# Power_supply.net
KiCad netlist of a schematic drawn in Altium Designer
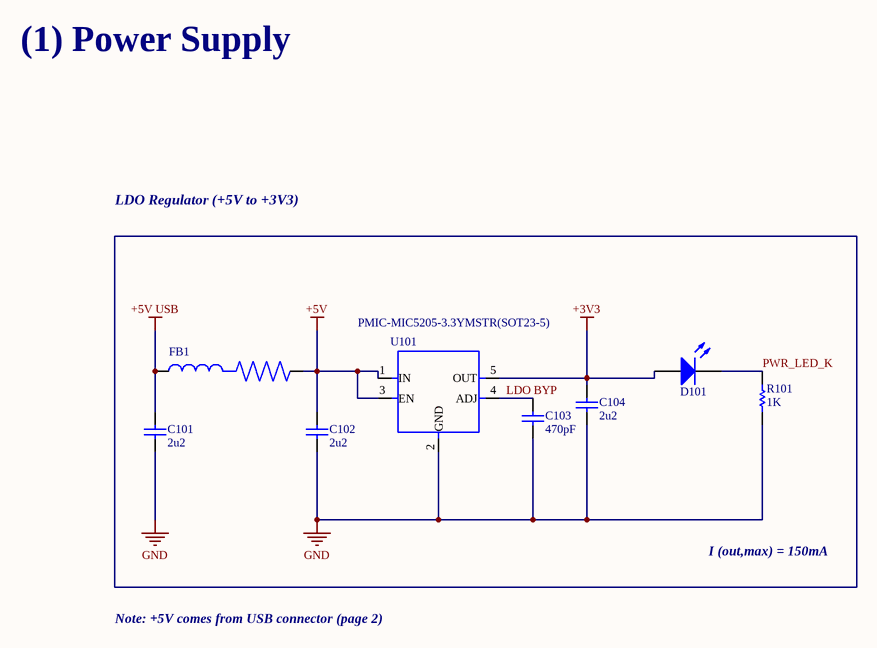
[diagram p0: Power_supply.SchDoc]

(export (version "E")
  (design (tool "Eeschema 10.0.6"))
  (components
    (comp (ref "C101")
      (value "2u2")
      (footprint "CAP-SM-0805")
      (description "Capacitor")
      (fields (field (name "Comment") "Cap Non-Pol SMD"))
      (libsource (lib "PIF_Library") (part "Cap Non-Pol SMD"))
    )
    (comp (ref "C102")
      (value "2u2")
      (footprint "CAP-SM-0805")
      (description "Capacitor")
      (fields (field (name "Comment") "Cap Non-Pol SMD"))
      (libsource (lib "PIF_Library") (part "Cap Non-Pol SMD"))
    )
    (comp (ref "C103")
      (value "470pF")
      (footprint "CAP-SM-0805")
      (description "Capacitor")
      (fields (field (name "Comment") "Cap Non-Pol SMD"))
      (libsource (lib "PIF_Library") (part "Cap Non-Pol SMD"))
    )
    (comp (ref "C104")
      (value "2u2")
      (footprint "CAP-SM-0805")
      (description "Capacitor")
      (fields (field (name "Comment") "Cap Non-Pol SMD"))
      (libsource (lib "PIF_Library") (part "Cap Non-Pol SMD"))
    )
    (comp (ref "D101")
      (value "LED SMD")
      (footprint "LED_0603_Blue")
      (description "LED")
      (libsource (lib "PIF_Library") (part "LED SMD"))
    )
    (comp (ref "FB1")
      (value "~")
      (footprint "BEADC0603X33N")
      (description "Ferrite Bead")
      (fields (field (name "MF") "Murata") (field (name "MP") "BLM03HD331SZ1D"))
      (libsource (lib "BLM03HD331SZ1D") (part "BLM03HD331SZ1D"))
    )
    (comp (ref "R101")
      (value "1K")
      (footprint "RES-SM-0603")
      (description "Resistor")
      (fields (field (name "Comment") "RESISTOR SMD"))
      (libsource (lib "PIF_Library") (part "RESISTOR SMD"))
    )
    (comp (ref "U101")
      (value "PMIC-MIC5205-3.3YMSTR(SOT23-5)")
      (footprint "SOT-23-5")
      (description "Linear Voltage Regulator IC Positive Fixed 1 Output 150mA SOT-23-5")
      (fields (field (name "MF") "Microchip") (field (name "MP") "MIC5205-3.3YM5-TR"))
      (libsource (lib "PMIC-MIC5205-3.3YMSTR_SOT23-5_") (part "PMIC-MIC5205-3.3YMSTR(SOT23-5)"))
    )
  )
  (nets
    (net (code "1") (name "+3V3") (class "Default")
      (node (ref "C104") (pin "2") (pinfunction "2_2") (pintype "passive"))
      (node (ref "D101") (pin "1") (pinfunction "A_1") (pintype "passive"))
      (node (ref "U101") (pin "5") (pinfunction "OUT_5") (pintype "bidirectional"))
    )
    (net (code "2") (name "+5V") (class "Default")
      (node (ref "C102") (pin "2") (pinfunction "2_2") (pintype "passive"))
      (node (ref "FB1") (pin "2") (pinfunction "2_2") (pintype "passive"))
      (node (ref "U101") (pin "1") (pinfunction "IN_1") (pintype "bidirectional"))
      (node (ref "U101") (pin "3") (pinfunction "EN_3") (pintype "bidirectional"))
    )
    (net (code "3") (name "+5V USB") (class "Default")
      (node (ref "C101") (pin "2") (pinfunction "2_2") (pintype "passive"))
      (node (ref "FB1") (pin "1") (pinfunction "1_1") (pintype "passive"))
    )
    (net (code "4") (name "/LDO BYP") (class "Default")
      (node (ref "C103") (pin "2") (pinfunction "2_2") (pintype "passive"))
      (node (ref "U101") (pin "4") (pinfunction "ADJ_4") (pintype "bidirectional"))
    )
    (net (code "5") (name "/PWR_LED_K") (class "Default")
      (node (ref "D101") (pin "2") (pinfunction "K_2") (pintype "passive"))
      (node (ref "R101") (pin "2") (pinfunction "2_2") (pintype "passive"))
    )
    (net (code "6") (name "GND") (class "Default")
      (node (ref "C101") (pin "1") (pinfunction "1_1") (pintype "passive"))
      (node (ref "C102") (pin "1") (pinfunction "1_1") (pintype "passive"))
      (node (ref "C103") (pin "1") (pinfunction "1_1") (pintype "passive"))
      (node (ref "C104") (pin "1") (pinfunction "1_1") (pintype "passive"))
      (node (ref "R101") (pin "1") (pinfunction "1_1") (pintype "passive"))
      (node (ref "U101") (pin "2") (pinfunction "GND_2") (pintype "bidirectional"))
    )
  )
)
